# WiF14Tao.net
KiCad netlist of a schematic drawn in Altium Designer
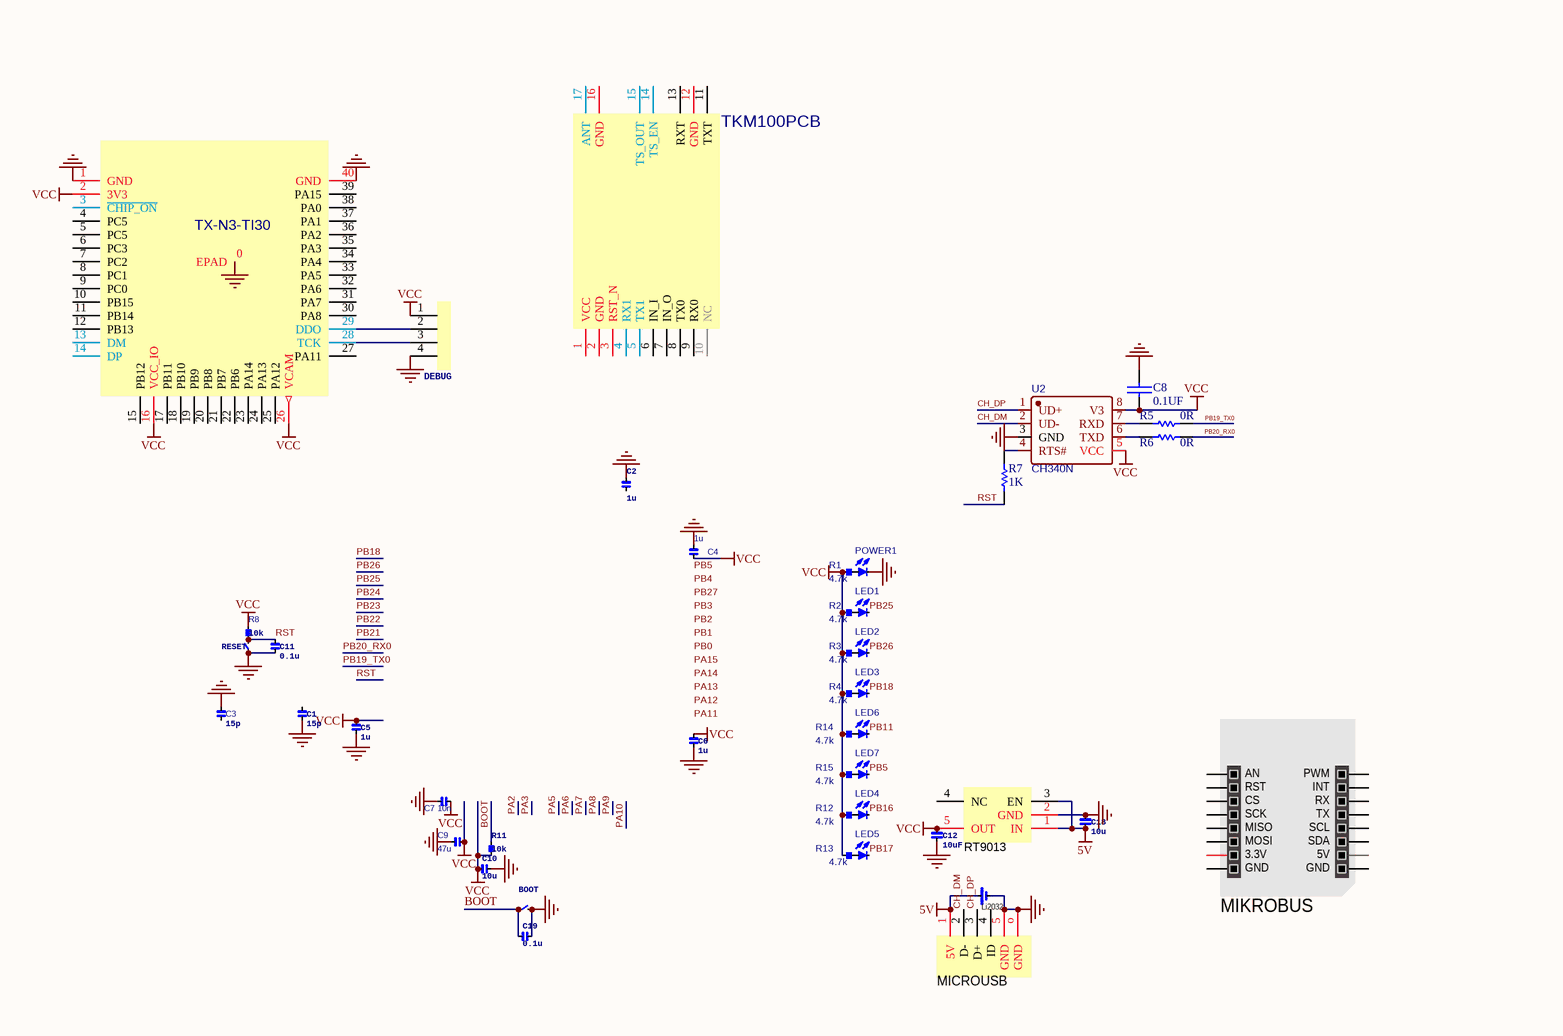
[diagram p0: WiF14Tao.SchDoc]

(export (version "E")
  (design (tool "Eeschema 10.0.6"))
  (components
    (comp (ref "BOOT") (value "~") (libsource (lib "altium-import") (part "root_0_key_")))
    (comp (ref "C1") (value "15p") (footprint "0603") (libsource (lib "altium-import") (part "root_3_C_")))
    (comp (ref "C2") (value "1u") (footprint "0603") (libsource (lib "") (part "root_1_C__1")))
    (comp (ref "C3") (value "15p") (footprint "0603") (libsource (lib "") (part "root_1_C__1")))
    (comp (ref "C4") (value "1u") (footprint "0603") (libsource (lib "altium-import") (part "root_3_C_")))
    (comp (ref "C5") (value "1u") (footprint "0603") (libsource (lib "altium-import") (part "root_3_C_")))
    (comp (ref "C6") (value "1u") (footprint "0603") (libsource (lib "altium-import") (part "root_3_C_")))
    (comp (ref "C7") (value "10n") (footprint "0603") (libsource (lib "altium-import") (part "root_0_C_")))
    (comp (ref "C8")
      (value "0.1UF")
      (footprint "C 0603_L")
      (description "Capacitor")
      (libsource (lib "*") (part "CAP"))
    )
    (comp (ref "C9") (value "47u") (footprint "0805") (libsource (lib "altium-import") (part "root_2_C_")))
    (comp (ref "C10") (value "10u") (footprint "0603") (libsource (lib "altium-import") (part "root_0_C_")))
    (comp (ref "C11") (value "0.1u") (footprint "0603") (libsource (lib "altium-import") (part "root_3_C_")))
    (comp (ref "C12") (value "10uF") (footprint "1206") (libsource (lib "") (part "root_3_C__1")))
    (comp (ref "C18") (value "10u") (footprint "1206") (libsource (lib "altium-import") (part "root_1_C_")))
    (comp (ref "C19") (value "0.1u") (footprint "0603") (libsource (lib "altium-import") (part "root_0_C_")))
    (comp (ref "DEBUG") (value "DEBUG") (libsource (lib "WiF14Tao") (part "DEBUG")))
    (comp (ref "LED1") (value "~") (footprint "0603") (libsource (lib "altium-import") (part "root_0_LED0_")))
    (comp (ref "LED2") (value "~") (footprint "0603") (libsource (lib "altium-import") (part "root_0_LED0_")))
    (comp (ref "LED3") (value "~") (footprint "0603") (libsource (lib "altium-import") (part "root_0_LED0_")))
    (comp (ref "LED4") (value "~") (footprint "0603") (libsource (lib "altium-import") (part "root_0_LED0_")))
    (comp (ref "LED5") (value "~") (footprint "0603") (libsource (lib "altium-import") (part "root_0_LED0_")))
    (comp (ref "LED6") (value "~") (footprint "0603") (libsource (lib "altium-import") (part "root_0_LED0_")))
    (comp (ref "LED7") (value "~") (footprint "0603") (libsource (lib "altium-import") (part "root_0_LED0_")))
    (comp (ref "Li2032") (value "~") (libsource (lib "altium-import") (part "root_0_Li2032_")))
    (comp (ref "MICROUSB")
      (value "~")
      (footprint "MICROUSB")
      (libsource (lib "altium-import") (part "root_1_MICROUSB_"))
    )
    (comp (ref "MIKROBUS")
      (value "~")
      (footprint "MIKROBUS")
      (libsource (lib "altium-import") (part "root_0_MIKROBUS_"))
    )
    (comp (ref "POWER1")
      (value "~")
      (footprint "0603")
      (libsource (lib "altium-import") (part "root_0_LED0_"))
    )
    (comp (ref "R1") (value "4.7k") (footprint "0603") (libsource (lib "altium-import") (part "root_2_R_")))
    (comp (ref "R2") (value "4.7k") (footprint "0603") (libsource (lib "altium-import") (part "root_2_R_")))
    (comp (ref "R3") (value "4.7k") (footprint "0603") (libsource (lib "altium-import") (part "root_2_R_")))
    (comp (ref "R4") (value "4.7k") (footprint "0603") (libsource (lib "altium-import") (part "root_2_R_")))
    (comp (ref "R5")
      (value "0R")
      (footprint "R 0603_L")
      (description "Resistor")
      (fields (field (name "PUBLISHER") "Altium Limited"))
      (libsource (lib "Miscellaneous Devices") (part "Res1"))
    )
    (comp (ref "R6")
      (value "0R")
      (footprint "R 0603_L")
      (description "Resistor")
      (fields (field (name "PUBLISHER") "Altium Limited"))
      (libsource (lib "Miscellaneous Devices") (part "Res1"))
    )
    (comp (ref "R7")
      (value "1K")
      (footprint "R 0603_L")
      (description "Resistor")
      (fields (field (name "PUBLISHER") "Altium Limited"))
      (libsource (lib "Miscellaneous Devices") (part "Res1"))
    )
    (comp (ref "R8") (value "10k") (footprint "0603") (libsource (lib "altium-import") (part "root_3_R_")))
    (comp (ref "R11") (value "10k") (footprint "0603") (libsource (lib "altium-import") (part "root_1_R_")))
    (comp (ref "R12") (value "4.7k") (footprint "0603") (libsource (lib "altium-import") (part "root_2_R_")))
    (comp (ref "R13") (value "4.7k") (footprint "0603") (libsource (lib "altium-import") (part "root_2_R_")))
    (comp (ref "R14") (value "4.7k") (footprint "0603") (libsource (lib "altium-import") (part "root_2_R_")))
    (comp (ref "R15") (value "4.7k") (footprint "0603") (libsource (lib "altium-import") (part "root_2_R_")))
    (comp (ref "RESET") (value "~") (libsource (lib "altium-import") (part "root_1_key_")))
    (comp (ref "RT9013")
      (value "~")
      (footprint "SGM2028")
      (libsource (lib "altium-import") (part "root_2_SGM2028_"))
    )
    (comp (ref "TKM100PCB") (value "~") (libsource (lib "altium-import") (part "root_0_TKM100PCB_")))
    (comp (ref "TX-N3-TI30") (value "TX-N3-TI30") (libsource (lib "WiF14Tao") (part "TX-N3-TI30")))
    (comp (ref "U2")
      (value "CH340N")
      (footprint "SOP8_L")
      (fields (field (name "BOM_SUPPLIER PART") "C506813") (field (name "CONTRIBUTOR") "LCSC"))
      (libsource (lib "Schlib1") (part "CH340N"))
    )
  )
  (nets
    (net (code "1") (name "/BOOT") (class "Default")
      (node (ref "BOOT") (pin "1") (pinfunction "1_1") (pintype "passive"))
      (node (ref "C19") (pin "1") (pinfunction "1_1") (pintype "passive"))
      (node (ref "R11") (pin "2") (pinfunction "2_2") (pintype "passive"))
    )
    (net (code "2") (name "/CH_DM") (class "Default")
      (node (ref "MICROUSB") (pin "2") (pinfunction "D-_2") (pintype "passive"))
      (node (ref "U2") (pin "2") (pinfunction "UD-_2") (pintype "passive"))
    )
    (net (code "3") (name "/CH_DP") (class "Default")
      (node (ref "MICROUSB") (pin "3") (pinfunction "D+_3") (pintype "passive"))
      (node (ref "U2") (pin "1") (pinfunction "UD+_1") (pintype "passive"))
    )
    (net (code "22") (name "/PB5") (class "Default") (node (ref "LED7") (pin "2") (pintype "passive")))
    (net (code "23") (name "/PB11") (class "Default") (node (ref "LED6") (pin "2") (pintype "passive")))
    (net (code "24") (name "/PB16") (class "Default") (node (ref "LED4") (pin "2") (pintype "passive")))
    (net (code "25") (name "/PB17") (class "Default") (node (ref "LED5") (pin "2") (pintype "passive")))
    (net (code "26") (name "/PB18") (class "Default") (node (ref "LED3") (pin "2") (pintype "passive")))
    (net (code "27") (name "/PB19_TX0") (class "Default")
      (node (ref "R5") (pin "2") (pinfunction "2_2") (pintype "passive"))
    )
    (net (code "28") (name "/PB20_RX0") (class "Default")
      (node (ref "R6") (pin "2") (pinfunction "2_2") (pintype "passive"))
    )
    (net (code "33") (name "/PB25") (class "Default") (node (ref "LED1") (pin "2") (pintype "passive")))
    (net (code "34") (name "/PB26") (class "Default") (node (ref "LED2") (pin "2") (pintype "passive")))
    (net (code "36") (name "/RST") (class "Default")
      (node (ref "C11") (pin "1") (pinfunction "1_1") (pintype "passive"))
      (node (ref "R7") (pin "1") (pinfunction "1_1") (pintype "passive"))
      (node (ref "R8") (pin "2") (pinfunction "2_2") (pintype "passive"))
      (node (ref "RESET") (pin "2") (pinfunction "2_2") (pintype "passive"))
    )
    (net (code "37") (name "5V") (class "Default")
      (node (ref "C18") (pin "1") (pinfunction "1_1") (pintype "passive"))
      (node (ref "Li2032") (pin "1") (pinfunction "1_1") (pintype "passive"))
      (node (ref "MICROUSB") (pin "1") (pinfunction "5V_1") (pintype "passive"))
      (node (ref "RT9013") (pin "1") (pinfunction "IN_1") (pintype "passive"))
      (node (ref "RT9013") (pin "3") (pinfunction "EN_3") (pintype "passive"))
    )
    (net (code "38") (name "GND") (class "Default")
      (node (ref "BOOT") (pin "2") (pinfunction "2_2") (pintype "passive"))
      (node (ref "C1") (pin "2") (pinfunction "2_2") (pintype "passive"))
      (node (ref "C10") (pin "2") (pinfunction "2_2") (pintype "passive"))
      (node (ref "C11") (pin "2") (pinfunction "2_2") (pintype "passive"))
      (node (ref "C12") (pin "2") (pinfunction "2_2") (pintype "passive"))
      (node (ref "C18") (pin "2") (pinfunction "2_2") (pintype "passive"))
      (node (ref "C19") (pin "2") (pinfunction "2_2") (pintype "passive"))
      (node (ref "C2") (pin "2") (pinfunction "2_2") (pintype "passive"))
      (node (ref "C3") (pin "2") (pinfunction "2_2") (pintype "passive"))
      (node (ref "C4") (pin "1") (pinfunction "1_1") (pintype "passive"))
      (node (ref "C5") (pin "2") (pinfunction "2_2") (pintype "passive"))
      (node (ref "C6") (pin "2") (pinfunction "2_2") (pintype "passive"))
      (node (ref "C7") (pin "1") (pinfunction "1_1") (pintype "passive"))
      (node (ref "C8") (pin "1") (pinfunction "1_1") (pintype "passive"))
      (node (ref "C9") (pin "2") (pinfunction "2_2") (pintype "passive"))
      (node (ref "DEBUG") (pin "4") (pintype "passive"))
      (node (ref "Li2032") (pin "2") (pinfunction "2_2") (pintype "passive"))
      (node (ref "MICROUSB") (pin "5") (pinfunction "GND_5") (pintype "passive"))
      (node (ref "MICROUSB") (pin "o") (pinfunction "GND_o") (pintype "passive"))
      (node (ref "POWER1") (pin "2") (pintype "passive"))
      (node (ref "RESET") (pin "1") (pinfunction "1_1") (pintype "passive"))
      (node (ref "RT9013") (pin "2") (pinfunction "GND_2") (pintype "passive"))
      (node (ref "TX-N3-TI30") (pin "0") (pinfunction "EPAD_0") (pintype "passive"))
      (node (ref "TX-N3-TI30") (pin "1") (pinfunction "GND_1") (pintype "passive"))
      (node (ref "TX-N3-TI30") (pin "40") (pinfunction "GND_40") (pintype "passive"))
      (node (ref "U2") (pin "3") (pinfunction "GND_3") (pintype "passive"))
    )
    (net (code "39") (name "Net-(LED1-Pad1)") (class "Default")
      (node (ref "LED1") (pin "1") (pintype "passive"))
      (node (ref "R2") (pin "1") (pinfunction "1_1") (pintype "passive"))
    )
    (net (code "40") (name "Net-(LED2-Pad1)") (class "Default")
      (node (ref "LED2") (pin "1") (pintype "passive"))
      (node (ref "R3") (pin "1") (pinfunction "1_1") (pintype "passive"))
    )
    (net (code "41") (name "Net-(LED3-Pad1)") (class "Default")
      (node (ref "LED3") (pin "1") (pintype "passive"))
      (node (ref "R4") (pin "1") (pinfunction "1_1") (pintype "passive"))
    )
    (net (code "42") (name "Net-(LED4-Pad1)") (class "Default")
      (node (ref "LED4") (pin "1") (pintype "passive"))
      (node (ref "R12") (pin "1") (pinfunction "1_1") (pintype "passive"))
    )
    (net (code "43") (name "Net-(LED5-Pad1)") (class "Default")
      (node (ref "LED5") (pin "1") (pintype "passive"))
      (node (ref "R13") (pin "1") (pinfunction "1_1") (pintype "passive"))
    )
    (net (code "44") (name "Net-(LED6-Pad1)") (class "Default")
      (node (ref "LED6") (pin "1") (pintype "passive"))
      (node (ref "R14") (pin "1") (pinfunction "1_1") (pintype "passive"))
    )
    (net (code "45") (name "Net-(LED7-Pad1)") (class "Default")
      (node (ref "LED7") (pin "1") (pintype "passive"))
      (node (ref "R15") (pin "1") (pinfunction "1_1") (pintype "passive"))
    )
    (net (code "46") (name "Net-(POWER1-Pad1)") (class "Default")
      (node (ref "POWER1") (pin "1") (pintype "passive"))
      (node (ref "R1") (pin "1") (pinfunction "1_1") (pintype "passive"))
    )
    (net (code "47") (name "Net-(TX-N3-TI30-DDO)") (class "Default")
      (node (ref "DEBUG") (pin "2") (pintype "passive"))
      (node (ref "TX-N3-TI30") (pin "29") (pinfunction "DDO_29") (pintype "passive"))
    )
    (net (code "48") (name "Net-(TX-N3-TI30-TCK)") (class "Default")
      (node (ref "DEBUG") (pin "3") (pintype "passive"))
      (node (ref "TX-N3-TI30") (pin "28") (pinfunction "TCK_28") (pintype "passive"))
    )
    (net (code "49") (name "Net-(U2-RTS#)") (class "Default")
      (node (ref "R7") (pin "2") (pinfunction "2_2") (pintype "passive"))
      (node (ref "U2") (pin "4") (pinfunction "RTS#_4") (pintype "passive"))
    )
    (net (code "50") (name "Net-(U2-RXD)") (class "Default")
      (node (ref "R5") (pin "1") (pinfunction "1_1") (pintype "passive"))
      (node (ref "U2") (pin "7") (pinfunction "RXD_7") (pintype "passive"))
    )
    (net (code "51") (name "Net-(U2-TXD)") (class "Default")
      (node (ref "R6") (pin "1") (pinfunction "1_1") (pintype "passive"))
      (node (ref "U2") (pin "6") (pinfunction "TXD_6") (pintype "passive"))
    )
    (net (code "52") (name "VCC") (class "Default")
      (node (ref "C10") (pin "1") (pinfunction "1_1") (pintype "passive"))
      (node (ref "C12") (pin "1") (pinfunction "1_1") (pintype "passive"))
      (node (ref "C4") (pin "2") (pinfunction "2_2") (pintype "passive"))
      (node (ref "C5") (pin "1") (pinfunction "1_1") (pintype "passive"))
      (node (ref "C6") (pin "1") (pinfunction "1_1") (pintype "passive"))
      (node (ref "C7") (pin "2") (pinfunction "2_2") (pintype "passive"))
      (node (ref "C8") (pin "2") (pinfunction "2_2") (pintype "passive"))
      (node (ref "C9") (pin "1") (pinfunction "1_1") (pintype "passive"))
      (node (ref "DEBUG") (pin "1") (pintype "passive"))
      (node (ref "R1") (pin "2") (pinfunction "2_2") (pintype "passive"))
      (node (ref "R11") (pin "1") (pinfunction "1_1") (pintype "passive"))
      (node (ref "R12") (pin "2") (pinfunction "2_2") (pintype "passive"))
      (node (ref "R13") (pin "2") (pinfunction "2_2") (pintype "passive"))
      (node (ref "R14") (pin "2") (pinfunction "2_2") (pintype "passive"))
      (node (ref "R15") (pin "2") (pinfunction "2_2") (pintype "passive"))
      (node (ref "R2") (pin "2") (pinfunction "2_2") (pintype "passive"))
      (node (ref "R3") (pin "2") (pinfunction "2_2") (pintype "passive"))
      (node (ref "R4") (pin "2") (pinfunction "2_2") (pintype "passive"))
      (node (ref "R8") (pin "1") (pinfunction "1_1") (pintype "passive"))
      (node (ref "RT9013") (pin "5") (pinfunction "OUT_5") (pintype "passive"))
      (node (ref "TX-N3-TI30") (pin "16") (pinfunction "VCC_IO_16") (pintype "passive"))
      (node (ref "TX-N3-TI30") (pin "2") (pinfunction "3V3_2") (pintype "passive"))
      (node (ref "TX-N3-TI30") (pin "26") (pinfunction "VCAM_26") (pintype "output"))
      (node (ref "U2") (pin "5") (pinfunction "VCC_5") (pintype "passive"))
      (node (ref "U2") (pin "8") (pinfunction "V3_8") (pintype "passive"))
    )
    (net (code "53") (name "unconnected-(C1-Pad1)") (class "Default")
      (node (ref "C1") (pin "1") (pinfunction "1_1") (pintype "passive"))
    )
    (net (code "54") (name "unconnected-(C2-Pad1)") (class "Default")
      (node (ref "C2") (pin "1") (pinfunction "1_1") (pintype "passive"))
    )
    (net (code "55") (name "unconnected-(C3-Pad1)") (class "Default")
      (node (ref "C3") (pin "1") (pinfunction "1_1") (pintype "passive"))
    )
    (net (code "56") (name "unconnected-(MICROUSB-ID-Pad4)") (class "Default")
      (node (ref "MICROUSB") (pin "4") (pinfunction "ID_4") (pintype "passive"))
    )
    (net (code "57") (name "unconnected-(MIKROBUS-3.3V-Pad7)") (class "Default")
      (node (ref "MIKROBUS") (pin "7") (pinfunction "3.3V_7") (pintype "passive"))
    )
    (net (code "58") (name "unconnected-(MIKROBUS-5V-Pad10)") (class "Default")
      (node (ref "MIKROBUS") (pin "10") (pinfunction "5V_10") (pintype "passive"))
    )
    (net (code "59") (name "unconnected-(MIKROBUS-AN-Pad1)") (class "Default")
      (node (ref "MIKROBUS") (pin "1") (pinfunction "AN_1") (pintype "passive"))
    )
    (net (code "60") (name "unconnected-(MIKROBUS-CS-Pad3)") (class "Default")
      (node (ref "MIKROBUS") (pin "3") (pinfunction "CS_3") (pintype "passive"))
    )
    (net (code "61") (name "unconnected-(MIKROBUS-GND-Pad8)") (class "Default")
      (node (ref "MIKROBUS") (pin "8") (pinfunction "GND_8") (pintype "passive"))
    )
    (net (code "62") (name "unconnected-(MIKROBUS-GND-Pad9)") (class "Default")
      (node (ref "MIKROBUS") (pin "9") (pinfunction "GND_9") (pintype "passive"))
    )
    (net (code "63") (name "unconnected-(MIKROBUS-INT-Pad15)") (class "Default")
      (node (ref "MIKROBUS") (pin "15") (pinfunction "INT_15") (pintype "passive"))
    )
    (net (code "64") (name "unconnected-(MIKROBUS-MISO-Pad5)") (class "Default")
      (node (ref "MIKROBUS") (pin "5") (pinfunction "MISO_5") (pintype "passive"))
    )
    (net (code "65") (name "unconnected-(MIKROBUS-MOSI-Pad6)") (class "Default")
      (node (ref "MIKROBUS") (pin "6") (pinfunction "MOSI_6") (pintype "passive"))
    )
    (net (code "66") (name "unconnected-(MIKROBUS-PWM-Pad16)") (class "Default")
      (node (ref "MIKROBUS") (pin "16") (pinfunction "PWM_16") (pintype "passive"))
    )
    (net (code "67") (name "unconnected-(MIKROBUS-RST-Pad2)") (class "Default")
      (node (ref "MIKROBUS") (pin "2") (pinfunction "RST_2") (pintype "passive"))
    )
    (net (code "68") (name "unconnected-(MIKROBUS-RX-Pad14)") (class "Default")
      (node (ref "MIKROBUS") (pin "14") (pinfunction "RX_14") (pintype "passive"))
    )
    (net (code "69") (name "unconnected-(MIKROBUS-SCK-Pad4)") (class "Default")
      (node (ref "MIKROBUS") (pin "4") (pinfunction "SCK_4") (pintype "passive"))
    )
    (net (code "70") (name "unconnected-(MIKROBUS-SCL-Pad12)") (class "Default")
      (node (ref "MIKROBUS") (pin "12") (pinfunction "SCL_12") (pintype "passive"))
    )
    (net (code "71") (name "unconnected-(MIKROBUS-SDA-Pad11)") (class "Default")
      (node (ref "MIKROBUS") (pin "11") (pinfunction "SDA_11") (pintype "passive"))
    )
    (net (code "72") (name "unconnected-(MIKROBUS-TX-Pad13)") (class "Default")
      (node (ref "MIKROBUS") (pin "13") (pinfunction "TX_13") (pintype "passive"))
    )
    (net (code "73") (name "unconnected-(RT9013-NC-Pad4)") (class "Default")
      (node (ref "RT9013") (pin "4") (pinfunction "NC_4") (pintype "passive"))
    )
    (net (code "74") (name "unconnected-(TKM100PCB-ANT-Pad17)") (class "Default")
      (node (ref "TKM100PCB") (pin "17") (pinfunction "ANT_17") (pintype "passive"))
    )
    (net (code "75") (name "unconnected-(TKM100PCB-GND-Pad2)") (class "Default")
      (node (ref "TKM100PCB") (pin "2") (pinfunction "GND_2") (pintype "passive"))
    )
    (net (code "76") (name "unconnected-(TKM100PCB-GND-Pad12)") (class "Default")
      (node (ref "TKM100PCB") (pin "12") (pinfunction "GND_12") (pintype "passive"))
    )
    (net (code "77") (name "unconnected-(TKM100PCB-GND-Pad16)") (class "Default")
      (node (ref "TKM100PCB") (pin "16") (pinfunction "GND_16") (pintype "passive"))
    )
    (net (code "78") (name "unconnected-(TKM100PCB-IN_I-Pad6)") (class "Default")
      (node (ref "TKM100PCB") (pin "6") (pinfunction "IN_I_6") (pintype "passive"))
    )
    (net (code "79") (name "unconnected-(TKM100PCB-IN_O-Pad7)") (class "Default")
      (node (ref "TKM100PCB") (pin "7") (pinfunction "IN_O_7") (pintype "passive"))
    )
    (net (code "80") (name "unconnected-(TKM100PCB-NC-Pad10)") (class "Default")
      (node (ref "TKM100PCB") (pin "10") (pinfunction "NC_10") (pintype "passive"))
    )
    (net (code "81") (name "unconnected-(TKM100PCB-RST_N-Pad3)") (class "Default")
      (node (ref "TKM100PCB") (pin "3") (pinfunction "RST_N_3") (pintype "passive"))
    )
    (net (code "82") (name "unconnected-(TKM100PCB-RX0-Pad9)") (class "Default")
      (node (ref "TKM100PCB") (pin "9") (pinfunction "RX0_9") (pintype "passive"))
    )
    (net (code "83") (name "unconnected-(TKM100PCB-RX1-Pad4)") (class "Default")
      (node (ref "TKM100PCB") (pin "4") (pinfunction "RX1_4") (pintype "passive"))
    )
    (net (code "84") (name "unconnected-(TKM100PCB-RXT-Pad13)") (class "Default")
      (node (ref "TKM100PCB") (pin "13") (pinfunction "RXT_13") (pintype "passive"))
    )
    (net (code "85") (name "unconnected-(TKM100PCB-TS_EN-Pad14)") (class "Default")
      (node (ref "TKM100PCB") (pin "14") (pinfunction "TS_EN_14") (pintype "passive"))
    )
    (net (code "86") (name "unconnected-(TKM100PCB-TS_OUT-Pad15)") (class "Default")
      (node (ref "TKM100PCB") (pin "15") (pinfunction "TS_OUT_15") (pintype "passive"))
    )
    (net (code "87") (name "unconnected-(TKM100PCB-TX0-Pad8)") (class "Default")
      (node (ref "TKM100PCB") (pin "8") (pinfunction "TX0_8") (pintype "passive"))
    )
    (net (code "88") (name "unconnected-(TKM100PCB-TX1-Pad5)") (class "Default")
      (node (ref "TKM100PCB") (pin "5") (pinfunction "TX1_5") (pintype "passive"))
    )
    (net (code "89") (name "unconnected-(TKM100PCB-TXT-Pad11)") (class "Default")
      (node (ref "TKM100PCB") (pin "11") (pinfunction "TXT_11") (pintype "passive"))
    )
    (net (code "90") (name "unconnected-(TKM100PCB-VCC-Pad1)") (class "Default")
      (node (ref "TKM100PCB") (pin "1") (pinfunction "VCC_1") (pintype "passive"))
    )
    (net (code "91") (name "unconnected-(TX-N3-TI30-DM-Pad13)") (class "Default")
      (node (ref "TX-N3-TI30") (pin "13") (pinfunction "DM_13") (pintype "passive"))
    )
    (net (code "92") (name "unconnected-(TX-N3-TI30-DP-Pad14)") (class "Default")
      (node (ref "TX-N3-TI30") (pin "14") (pinfunction "DP_14") (pintype "passive"))
    )
    (net (code "93") (name "unconnected-(TX-N3-TI30-PA0-Pad38)") (class "Default")
      (node (ref "TX-N3-TI30") (pin "38") (pinfunction "PA0_38") (pintype "passive"))
    )
    (net (code "94") (name "unconnected-(TX-N3-TI30-PA1-Pad37)") (class "Default")
      (node (ref "TX-N3-TI30") (pin "37") (pinfunction "PA1_37") (pintype "passive"))
    )
    (net (code "95") (name "unconnected-(TX-N3-TI30-PA2-Pad36)") (class "Default")
      (node (ref "TX-N3-TI30") (pin "36") (pinfunction "PA2_36") (pintype "passive"))
    )
    (net (code "96") (name "unconnected-(TX-N3-TI30-PA3-Pad35)") (class "Default")
      (node (ref "TX-N3-TI30") (pin "35") (pinfunction "PA3_35") (pintype "passive"))
    )
    (net (code "97") (name "unconnected-(TX-N3-TI30-PA4-Pad34)") (class "Default")
      (node (ref "TX-N3-TI30") (pin "34") (pinfunction "PA4_34") (pintype "passive"))
    )
    (net (code "98") (name "unconnected-(TX-N3-TI30-PA5-Pad33)") (class "Default")
      (node (ref "TX-N3-TI30") (pin "33") (pinfunction "PA5_33") (pintype "passive"))
    )
    (net (code "99") (name "unconnected-(TX-N3-TI30-PA6-Pad32)") (class "Default")
      (node (ref "TX-N3-TI30") (pin "32") (pinfunction "PA6_32") (pintype "passive"))
    )
    (net (code "100") (name "unconnected-(TX-N3-TI30-PA7-Pad31)") (class "Default")
      (node (ref "TX-N3-TI30") (pin "31") (pinfunction "PA7_31") (pintype "passive"))
    )
    (net (code "101") (name "unconnected-(TX-N3-TI30-PA8-Pad30)") (class "Default")
      (node (ref "TX-N3-TI30") (pin "30") (pinfunction "PA8_30") (pintype "passive"))
    )
    (net (code "102") (name "unconnected-(TX-N3-TI30-PA11-Pad27)") (class "Default")
      (node (ref "TX-N3-TI30") (pin "27") (pinfunction "PA11_27") (pintype "passive"))
    )
    (net (code "103") (name "unconnected-(TX-N3-TI30-PA12-Pad25)") (class "Default")
      (node (ref "TX-N3-TI30") (pin "25") (pinfunction "PA12_25") (pintype "passive"))
    )
    (net (code "104") (name "unconnected-(TX-N3-TI30-PA13-Pad24)") (class "Default")
      (node (ref "TX-N3-TI30") (pin "24") (pinfunction "PA13_24") (pintype "passive"))
    )
    (net (code "105") (name "unconnected-(TX-N3-TI30-PA14-Pad23)") (class "Default")
      (node (ref "TX-N3-TI30") (pin "23") (pinfunction "PA14_23") (pintype "passive"))
    )
    (net (code "106") (name "unconnected-(TX-N3-TI30-PA15-Pad39)") (class "Default")
      (node (ref "TX-N3-TI30") (pin "39") (pinfunction "PA15_39") (pintype "passive"))
    )
    (net (code "107") (name "unconnected-(TX-N3-TI30-PB6-Pad22)") (class "Default")
      (node (ref "TX-N3-TI30") (pin "22") (pinfunction "PB6_22") (pintype "passive"))
    )
    (net (code "108") (name "unconnected-(TX-N3-TI30-PB7-Pad21)") (class "Default")
      (node (ref "TX-N3-TI30") (pin "21") (pinfunction "PB7_21") (pintype "passive"))
    )
    (net (code "109") (name "unconnected-(TX-N3-TI30-PB8-Pad20)") (class "Default")
      (node (ref "TX-N3-TI30") (pin "20") (pinfunction "PB8_20") (pintype "passive"))
    )
    (net (code "110") (name "unconnected-(TX-N3-TI30-PB9-Pad19)") (class "Default")
      (node (ref "TX-N3-TI30") (pin "19") (pinfunction "PB9_19") (pintype "passive"))
    )
    (net (code "111") (name "unconnected-(TX-N3-TI30-PB10-Pad18)") (class "Default")
      (node (ref "TX-N3-TI30") (pin "18") (pinfunction "PB10_18") (pintype "passive"))
    )
    (net (code "112") (name "unconnected-(TX-N3-TI30-PB11-Pad17)") (class "Default")
      (node (ref "TX-N3-TI30") (pin "17") (pinfunction "PB11_17") (pintype "passive"))
    )
    (net (code "113") (name "unconnected-(TX-N3-TI30-PB12-Pad15)") (class "Default")
      (node (ref "TX-N3-TI30") (pin "15") (pinfunction "PB12_15") (pintype "passive"))
    )
    (net (code "114") (name "unconnected-(TX-N3-TI30-PB13-Pad12)") (class "Default")
      (node (ref "TX-N3-TI30") (pin "12") (pinfunction "PB13_12") (pintype "passive"))
    )
    (net (code "115") (name "unconnected-(TX-N3-TI30-PB14-Pad11)") (class "Default")
      (node (ref "TX-N3-TI30") (pin "11") (pinfunction "PB14_11") (pintype "passive"))
    )
    (net (code "116") (name "unconnected-(TX-N3-TI30-PB15-Pad10)") (class "Default")
      (node (ref "TX-N3-TI30") (pin "10") (pinfunction "PB15_10") (pintype "passive"))
    )
    (net (code "117") (name "unconnected-(TX-N3-TI30-PC0-Pad9)") (class "Default")
      (node (ref "TX-N3-TI30") (pin "9") (pinfunction "PC0_9") (pintype "passive"))
    )
    (net (code "118") (name "unconnected-(TX-N3-TI30-PC1-Pad8)") (class "Default")
      (node (ref "TX-N3-TI30") (pin "8") (pinfunction "PC1_8") (pintype "passive"))
    )
    (net (code "119") (name "unconnected-(TX-N3-TI30-PC2-Pad7)") (class "Default")
      (node (ref "TX-N3-TI30") (pin "7") (pinfunction "PC2_7") (pintype "passive"))
    )
    (net (code "120") (name "unconnected-(TX-N3-TI30-PC3-Pad6)") (class "Default")
      (node (ref "TX-N3-TI30") (pin "6") (pinfunction "PC3_6") (pintype "passive"))
    )
    (net (code "121") (name "unconnected-(TX-N3-TI30-PC5-Pad4)") (class "Default")
      (node (ref "TX-N3-TI30") (pin "4") (pinfunction "PC5_4") (pintype "passive"))
    )
    (net (code "122") (name "unconnected-(TX-N3-TI30-PC5-Pad5)") (class "Default")
      (node (ref "TX-N3-TI30") (pin "5") (pinfunction "PC5_5") (pintype "passive"))
    )
    (net (code "123") (name "unconnected-(TX-N3-TI30-~{CHIP_ON}-Pad3)") (class "Default")
      (node (ref "TX-N3-TI30") (pin "3") (pinfunction "~{CHIP_ON}_3") (pintype "passive"))
    )
  )
)
